# design.net
KiCad netlist of a schematic drawn in Altium Designer
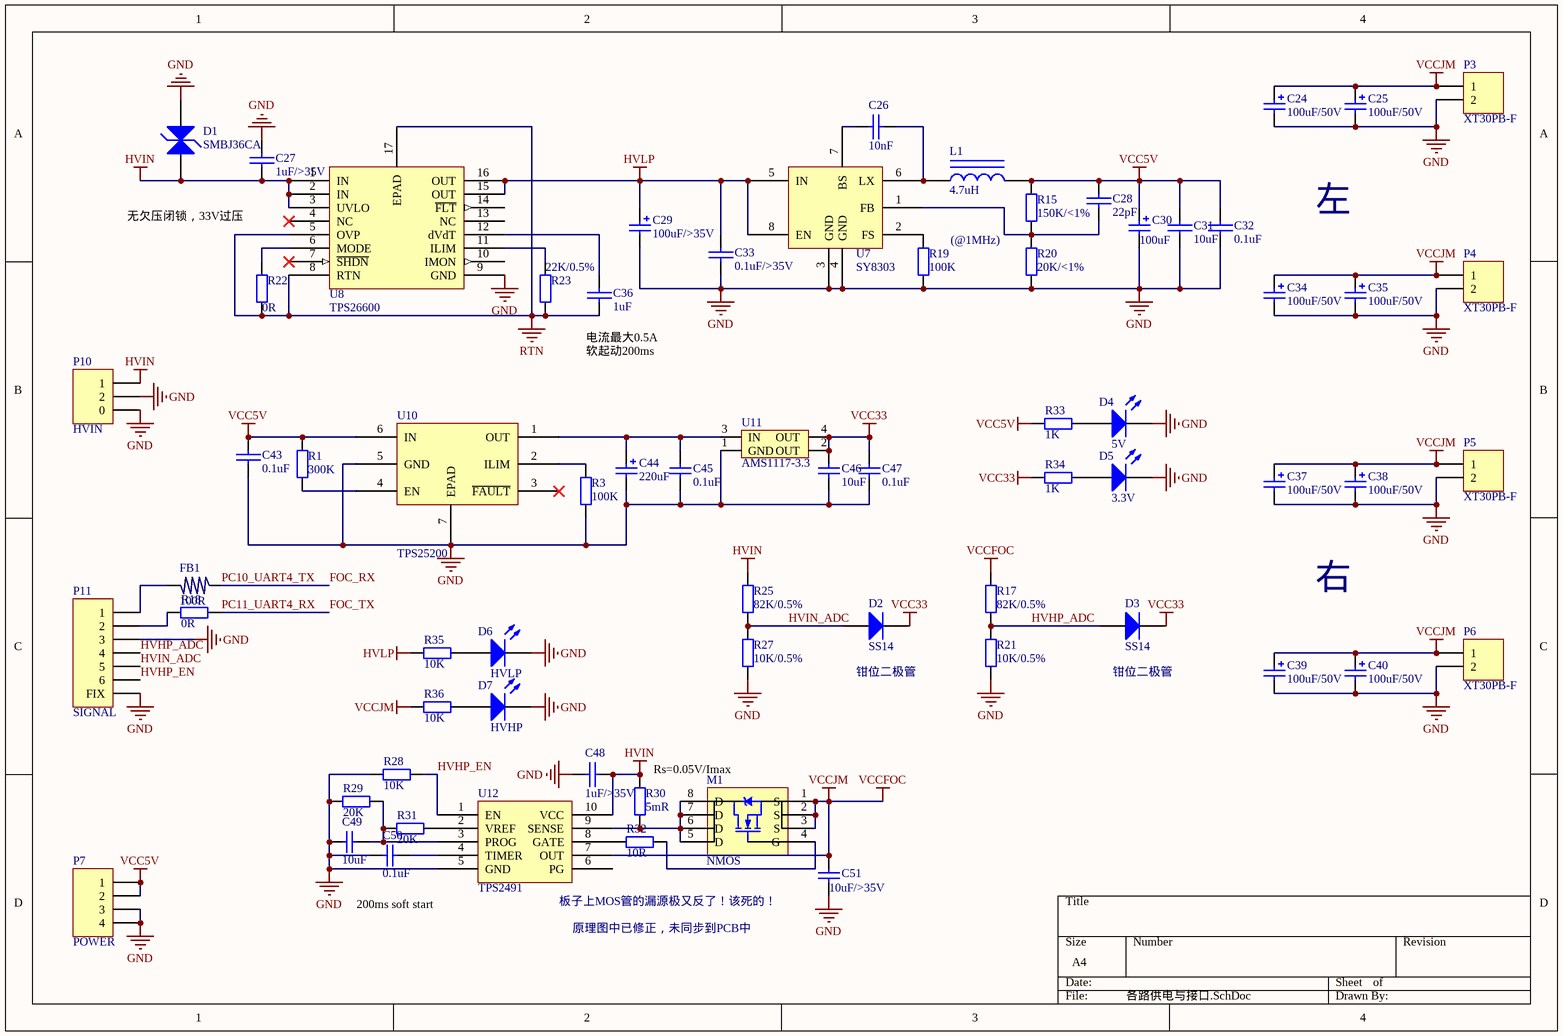
[diagram p0: 各路供电与接口.SchDoc]

(export (version "E")
  (design (tool "Eeschema 10.0.6"))
  (components
    (comp (ref "C24")
      (value "100uF/50V")
      (footprint "CS 6*6 - R")
      (description "Low ESR required")
      (fields (field (name "PUBLISHER") "Altium Limited"))
      (libsource (lib "Miscellaneous Devices") (part "Cap Pol2"))
    )
    (comp (ref "C25")
      (value "100uF/50V")
      (footprint "CS 6*6 - R")
      (description "Low ESR required")
      (fields (field (name "PUBLISHER") "Altium Limited"))
      (libsource (lib "Miscellaneous Devices") (part "Cap Pol2"))
    )
    (comp (ref "C26")
      (value "10nF")
      (footprint "C0805_M")
      (description "Capacitor")
      (libsource (lib "*") (part "CAP"))
    )
    (comp (ref "C27")
      (value "1uF/>35V")
      (footprint "C0805_M")
      (description "Capacitor")
      (libsource (lib "*") (part "CAP"))
    )
    (comp (ref "C28")
      (value "22pF")
      (footprint "C0805_M")
      (description "Capacitor")
      (libsource (lib "*") (part "CAP"))
    )
    (comp (ref "C29")
      (value "100uF/>35V")
      (footprint "CS 6*6 - R")
      (description "固态电容")
      (fields (field (name "PUBLISHER") "Altium Limited"))
      (libsource (lib "Miscellaneous Devices") (part "Cap Pol2"))
    )
    (comp (ref "C30")
      (value "100uF")
      (footprint "CS 6*6 - R")
      (description "固态电容")
      (fields (field (name "PUBLISHER") "Altium Limited"))
      (libsource (lib "Miscellaneous Devices") (part "Cap Pol2"))
    )
    (comp (ref "C31")
      (value "10uF")
      (footprint "C0805_M")
      (description "Capacitor")
      (libsource (lib "*") (part "CAP"))
    )
    (comp (ref "C32")
      (value "0.1uF")
      (footprint "C0805_M")
      (description "Capacitor")
      (libsource (lib "*") (part "CAP"))
    )
    (comp (ref "C33")
      (value "0.1uF/>35V")
      (footprint "C0805_M")
      (description "Capacitor")
      (libsource (lib "*") (part "CAP"))
    )
    (comp (ref "C34")
      (value "100uF/50V")
      (footprint "CS 6*6 - R")
      (description "Low ESR required")
      (fields (field (name "PUBLISHER") "Altium Limited"))
      (libsource (lib "Miscellaneous Devices") (part "Cap Pol2"))
    )
    (comp (ref "C35")
      (value "100uF/50V")
      (footprint "CS 6*6 - R")
      (description "Low ESR required")
      (fields (field (name "PUBLISHER") "Altium Limited"))
      (libsource (lib "Miscellaneous Devices") (part "Cap Pol2"))
    )
    (comp (ref "C36")
      (value "1uF")
      (footprint "C0805_M")
      (description "Capacitor")
      (libsource (lib "*") (part "CAP"))
    )
    (comp (ref "C37")
      (value "100uF/50V")
      (footprint "CS 6*6 - R")
      (description "Low ESR required")
      (fields (field (name "PUBLISHER") "Altium Limited"))
      (libsource (lib "Miscellaneous Devices") (part "Cap Pol2"))
    )
    (comp (ref "C38")
      (value "100uF/50V")
      (footprint "CS 6*6 - R")
      (description "Low ESR required")
      (fields (field (name "PUBLISHER") "Altium Limited"))
      (libsource (lib "Miscellaneous Devices") (part "Cap Pol2"))
    )
    (comp (ref "C39")
      (value "100uF/50V")
      (footprint "CS 6*6 - R")
      (description "Low ESR required")
      (fields (field (name "PUBLISHER") "Altium Limited"))
      (libsource (lib "Miscellaneous Devices") (part "Cap Pol2"))
    )
    (comp (ref "C40")
      (value "100uF/50V")
      (footprint "CS 6*6 - R")
      (description "Low ESR required")
      (fields (field (name "PUBLISHER") "Altium Limited"))
      (libsource (lib "Miscellaneous Devices") (part "Cap Pol2"))
    )
    (comp (ref "C43")
      (value "0.1uF")
      (footprint "C0805_M")
      (description "Capacitor")
      (libsource (lib "*") (part "CAP"))
    )
    (comp (ref "C44")
      (value "220uF")
      (footprint "CS 6*6 - R")
      (description "Polarized Capacitor (Axial)")
      (fields (field (name "PUBLISHER") "Altium Limited"))
      (libsource (lib "Miscellaneous Devices") (part "Cap Pol2"))
    )
    (comp (ref "C45")
      (value "0.1uF")
      (footprint "C0805_M")
      (description "Capacitor")
      (fields (field (name "PUBLISHER") "Altium Limited"))
      (libsource (lib "Miscellaneous Devices") (part "Cap"))
    )
    (comp (ref "C46")
      (value "10uF")
      (footprint "C0805_M")
      (description "Capacitor")
      (fields (field (name "PUBLISHER") "Altium Limited"))
      (libsource (lib "Miscellaneous Devices") (part "Cap"))
    )
    (comp (ref "C47")
      (value "0.1uF")
      (footprint "C0805_M")
      (description "Capacitor")
      (fields (field (name "PUBLISHER") "Altium Limited"))
      (libsource (lib "Miscellaneous Devices") (part "Cap"))
    )
    (comp (ref "C48")
      (value "1uF/>35V")
      (footprint "C0805_M")
      (description "Capacitor")
      (libsource (lib "*") (part "CAP"))
    )
    (comp (ref "C49")
      (value "10uF")
      (footprint "C0805_M")
      (description "Capacitor")
      (fields (field (name "PUBLISHER") "Altium Limited"))
      (libsource (lib "Miscellaneous Devices") (part "Cap"))
    )
    (comp (ref "C50")
      (value "0.1uF")
      (footprint "C0805_M")
      (description "Capacitor")
      (fields (field (name "PUBLISHER") "Altium Limited"))
      (libsource (lib "Miscellaneous Devices") (part "Cap"))
    )
    (comp (ref "C51")
      (value "10uF/>35V")
      (footprint "C0805_M")
      (description "Capacitor")
      (fields (field (name "PUBLISHER") "Altium Limited"))
      (libsource (lib "Miscellaneous Devices") (part "Cap"))
    )
    (comp (ref "D1")
      (value "SMBJ36CA")
      (footprint "1.07-二极管、整流桥:SMB")
      (libsource (lib "XL6005") (part "TVS"))
    )
    (comp (ref "D2")
      (value "SS14")
      (footprint "SOD-323")
      (description "Default Diode")
      (fields (field (name "PUBLISHER") "Altium Limited"))
      (libsource (lib "Miscellaneous Devices") (part "Diode"))
    )
    (comp (ref "D3")
      (value "SS14")
      (footprint "SOD-323")
      (description "Default Diode")
      (fields (field (name "PUBLISHER") "Altium Limited"))
      (libsource (lib "Miscellaneous Devices") (part "Diode"))
    )
    (comp (ref "D4")
      (value "5V")
      (footprint "LED0805_G")
      (description "Typical RED GaAs LED")
      (fields (field (name "PUBLISHER") "Altium Limited"))
      (libsource (lib "Miscellaneous Devices") (part "LED1"))
    )
    (comp (ref "D5")
      (value "3.3V")
      (footprint "LED0805_G")
      (description "Typical RED GaAs LED")
      (fields (field (name "PUBLISHER") "Altium Limited"))
      (libsource (lib "Miscellaneous Devices") (part "LED1"))
    )
    (comp (ref "D6")
      (value "HVLP")
      (footprint "LED0805_G")
      (description "Typical RED GaAs LED")
      (fields (field (name "PUBLISHER") "Altium Limited"))
      (libsource (lib "Miscellaneous Devices") (part "LED1"))
    )
    (comp (ref "D7")
      (value "HVHP")
      (footprint "LED0805_G")
      (description "Typical RED GaAs LED")
      (fields (field (name "PUBLISHER") "Altium Limited"))
      (libsource (lib "Miscellaneous Devices") (part "LED1"))
    )
    (comp (ref "FB1") (value "100R") (footprint "R0805_M") (libsource (lib "EXPLORER") (part "L")))
    (comp (ref "L1")
      (value "4.7uH")
      (footprint "L-SMD-0630")
      (description "Magnetic-Core Inductor")
      (fields (field (name "PUBLISHER") "Altium Limited"))
      (libsource (lib "Miscellaneous Devices") (part "Inductor Iron"))
    )
    (comp (ref "M1") (value "NMOS") (footprint "DFN8L-5X6") (libsource (lib "XL6005") (part "NMOS_IC")))
    (comp (ref "P3")
      (value "XT30PB-F")
      (footprint "XT30PB-F")
      (description "Header, 2-Pin")
      (fields (field (name "PUBLISHER") "Altium Limited"))
      (libsource (lib "Miscellaneous Connectors") (part "Header 2"))
    )
    (comp (ref "P4")
      (value "XT30PB-F")
      (footprint "XT30PB-F")
      (description "Header, 2-Pin")
      (fields (field (name "PUBLISHER") "Altium Limited"))
      (libsource (lib "Miscellaneous Connectors") (part "Header 2"))
    )
    (comp (ref "P5")
      (value "XT30PB-F")
      (footprint "XT30PB-F")
      (description "Header, 2-Pin")
      (fields (field (name "PUBLISHER") "Altium Limited"))
      (libsource (lib "Miscellaneous Connectors") (part "Header 2"))
    )
    (comp (ref "P6")
      (value "XT30PB-F")
      (footprint "XT30PB-F")
      (description "Header, 2-Pin")
      (fields (field (name "PUBLISHER") "Altium Limited"))
      (libsource (lib "Miscellaneous Connectors") (part "Header 2"))
    )
    (comp (ref "P7")
      (value "POWER")
      (footprint "XH2.54-LI-4P")
      (description "Header, 4-Pin")
      (fields (field (name "PUBLISHER") "Altium Limited"))
      (libsource (lib "Miscellaneous Connectors") (part "Header 4"))
    )
    (comp (ref "P10")
      (value "HVIN")
      (footprint "XT60PW-M")
      (description "Header, 3-Pin")
      (fields (field (name "PUBLISHER") "Altium Limited"))
      (libsource (lib "Miscellaneous Connectors") (part "Header 3"))
    )
    (comp (ref "P11")
      (value "SIGNAL")
      (footprint "SH1.0-LT-6P")
      (description "Header, 7-Pin")
      (fields (field (name "PUBLISHER") "Altium Limited"))
      (libsource (lib "Miscellaneous Connectors") (part "Header 7"))
    )
    (comp (ref "R1")
      (value "300K")
      (footprint "R0805_M")
      (description "Resistor")
      (fields (field (name "PUBLISHER") "Altium Limited"))
      (libsource (lib "Miscellaneous Devices") (part "Res2"))
    )
    (comp (ref "R3")
      (value "100K")
      (footprint "R0805_M")
      (description "Resistor")
      (fields (field (name "PUBLISHER") "Altium Limited"))
      (libsource (lib "Miscellaneous Devices") (part "Res2"))
    )
    (comp (ref "R15")
      (value "150K/<1%")
      (footprint "R0805_M")
      (description "Resistor")
      (fields (field (name "PUBLISHER") "Altium Limited"))
      (libsource (lib "") (part "Res2_1"))
    )
    (comp (ref "R17")
      (value "82K/0.5%")
      (footprint "R0805_M")
      (description "Resistor")
      (fields (field (name "PUBLISHER") "Altium Limited"))
      (libsource (lib "") (part "Res2_1"))
    )
    (comp (ref "R18")
      (value "0R")
      (footprint "R0805_M")
      (description "Resistor")
      (fields (field (name "PUBLISHER") "Altium Limited"))
      (libsource (lib "") (part "Res2_2"))
    )
    (comp (ref "R19")
      (value "100K")
      (footprint "R0805_M")
      (description "Resistor")
      (fields (field (name "PUBLISHER") "Altium Limited"))
      (libsource (lib "") (part "Res2_1"))
    )
    (comp (ref "R20")
      (value "20K/<1%")
      (footprint "R0805_M")
      (description "Resistor")
      (fields (field (name "PUBLISHER") "Altium Limited"))
      (libsource (lib "") (part "Res2_1"))
    )
    (comp (ref "R21")
      (value "10K/0.5%")
      (footprint "R0805_M")
      (description "Resistor")
      (fields (field (name "PUBLISHER") "Altium Limited"))
      (libsource (lib "") (part "Res2_1"))
    )
    (comp (ref "R22")
      (value "0R")
      (footprint "R0805_M")
      (description "Resistor")
      (fields (field (name "PUBLISHER") "Altium Limited"))
      (libsource (lib "") (part "Res2_1"))
    )
    (comp (ref "R23")
      (value "22K/0.5%")
      (footprint "R0805_M")
      (description "Resistor")
      (fields (field (name "PUBLISHER") "Altium Limited"))
      (libsource (lib "") (part "Res2_1"))
    )
    (comp (ref "R25")
      (value "82K/0.5%")
      (footprint "R0805_M")
      (description "Resistor")
      (fields (field (name "PUBLISHER") "Altium Limited"))
      (libsource (lib "") (part "Res2_1"))
    )
    (comp (ref "R27")
      (value "10K/0.5%")
      (footprint "R0805_M")
      (description "Resistor")
      (fields (field (name "PUBLISHER") "Altium Limited"))
      (libsource (lib "") (part "Res2_1"))
    )
    (comp (ref "R28")
      (value "10K")
      (footprint "R0805_M")
      (description "Resistor")
      (fields (field (name "PUBLISHER") "Altium Limited"))
      (libsource (lib "") (part "Res2_2"))
    )
    (comp (ref "R29")
      (value "20K")
      (footprint "R0805_M")
      (description "Resistor")
      (fields (field (name "PUBLISHER") "Altium Limited"))
      (libsource (lib "") (part "Res2_2"))
    )
    (comp (ref "R30")
      (value "5mR")
      (footprint "R2512_M")
      (description "Resistor")
      (fields (field (name "PUBLISHER") "Altium Limited"))
      (libsource (lib "Miscellaneous Devices") (part "Res2"))
    )
    (comp (ref "R31")
      (value "20K")
      (footprint "R0805_M")
      (description "Resistor")
      (fields (field (name "PUBLISHER") "Altium Limited"))
      (libsource (lib "") (part "Res2_2"))
    )
    (comp (ref "R32")
      (value "10R")
      (footprint "R0805_M")
      (description "Resistor")
      (fields (field (name "PUBLISHER") "Altium Limited"))
      (libsource (lib "") (part "Res2_2"))
    )
    (comp (ref "R33")
      (value "1K")
      (footprint "R0805_M")
      (description "Resistor")
      (fields (field (name "PUBLISHER") "Altium Limited"))
      (libsource (lib "") (part "Res2_2"))
    )
    (comp (ref "R34")
      (value "1K")
      (footprint "R0805_M")
      (description "Resistor")
      (fields (field (name "PUBLISHER") "Altium Limited"))
      (libsource (lib "") (part "Res2_2"))
    )
    (comp (ref "R35")
      (value "10K")
      (footprint "R0805_M")
      (description "Resistor")
      (fields (field (name "PUBLISHER") "Altium Limited"))
      (libsource (lib "") (part "Res2_2"))
    )
    (comp (ref "R36")
      (value "10K")
      (footprint "R0805_M")
      (description "Resistor")
      (fields (field (name "PUBLISHER") "Altium Limited"))
      (libsource (lib "") (part "Res2_2"))
    )
    (comp (ref "U7") (value "SY8303") (footprint "SOT23-8L") (libsource (lib "7688A原理图封装") (part "SY8303")))
    (comp (ref "U8") (value "TPS26600") (footprint "ETSSOP16_M") (libsource (lib "XL6005") (part "TPS26600")))
    (comp (ref "U10")
      (value "TPS25200")
      (footprint "WSON-6")
      (libsource (lib "7688A原理图封装") (part "TPS25200"))
    )
    (comp (ref "U11")
      (value "AMS1117-3.3")
      (footprint "2.02-SOT封装:SOT223_M")
      (libsource (lib "Explorer STM32F407封装库") (part "AMS1117"))
    )
    (comp (ref "U12") (value "TPS2491") (footprint "VSSOP10") (libsource (lib "XL6005") (part "TPS2491")))
  )
  (nets
    (net (code "1") (name "/FOC_RX") (class "Default") (node (ref "FB1") (pin "1") (pintype "passive")))
    (net (code "2") (name "/FOC_TX") (class "Default")
      (node (ref "R18") (pin "1") (pinfunction "1_1") (pintype "passive"))
    )
    (net (code "3") (name "/HVHP_ADC") (class "Default")
      (node (ref "D3") (pin "1") (pinfunction "A_1") (pintype "passive"))
      (node (ref "P11") (pin "4") (pinfunction "4_4") (pintype "passive"))
      (node (ref "R17") (pin "2") (pinfunction "2_2") (pintype "passive"))
      (node (ref "R21") (pin "1") (pinfunction "1_1") (pintype "passive"))
    )
    (net (code "4") (name "/HVHP_EN") (class "Default")
      (node (ref "P11") (pin "6") (pinfunction "6_6") (pintype "passive"))
      (node (ref "R28") (pin "1") (pinfunction "1_1") (pintype "passive"))
      (node (ref "U12") (pin "1") (pinfunction "EN_1") (pintype "passive"))
    )
    (net (code "5") (name "/HVIN_ADC") (class "Default")
      (node (ref "D2") (pin "1") (pinfunction "A_1") (pintype "passive"))
      (node (ref "P11") (pin "5") (pinfunction "5_5") (pintype "passive"))
      (node (ref "R25") (pin "2") (pinfunction "2_2") (pintype "passive"))
      (node (ref "R27") (pin "1") (pinfunction "1_1") (pintype "passive"))
    )
    (net (code "6") (name "GND") (class "Default")
      (node (ref "C24") (pin "2") (pinfunction "2_2") (pintype "passive"))
      (node (ref "C25") (pin "2") (pinfunction "2_2") (pintype "passive"))
      (node (ref "C27") (pin "2") (pinfunction "2_2") (pintype "passive"))
      (node (ref "C29") (pin "2") (pinfunction "2_2") (pintype "passive"))
      (node (ref "C30") (pin "2") (pinfunction "2_2") (pintype "passive"))
      (node (ref "C31") (pin "1") (pinfunction "1_1") (pintype "passive"))
      (node (ref "C32") (pin "1") (pinfunction "1_1") (pintype "passive"))
      (node (ref "C33") (pin "1") (pinfunction "1_1") (pintype "passive"))
      (node (ref "C34") (pin "2") (pinfunction "2_2") (pintype "passive"))
      (node (ref "C35") (pin "2") (pinfunction "2_2") (pintype "passive"))
      (node (ref "C37") (pin "2") (pinfunction "2_2") (pintype "passive"))
      (node (ref "C38") (pin "2") (pinfunction "2_2") (pintype "passive"))
      (node (ref "C39") (pin "2") (pinfunction "2_2") (pintype "passive"))
      (node (ref "C40") (pin "2") (pinfunction "2_2") (pintype "passive"))
      (node (ref "C43") (pin "2") (pinfunction "2_2") (pintype "passive"))
      (node (ref "C44") (pin "2") (pinfunction "2_2") (pintype "passive"))
      (node (ref "C45") (pin "1") (pinfunction "1_1") (pintype "passive"))
      (node (ref "C46") (pin "1") (pinfunction "1_1") (pintype "passive"))
      (node (ref "C47") (pin "1") (pinfunction "1_1") (pintype "passive"))
      (node (ref "C48") (pin "1") (pinfunction "1_1") (pintype "passive"))
      (node (ref "C49") (pin "1") (pinfunction "1_1") (pintype "passive"))
      (node (ref "C50") (pin "1") (pinfunction "1_1") (pintype "passive"))
      (node (ref "C51") (pin "1") (pinfunction "1_1") (pintype "passive"))
      (node (ref "D1") (pin "1") (pinfunction "A_1") (pintype "passive"))
      (node (ref "D4") (pin "2") (pinfunction "K_2") (pintype "passive"))
      (node (ref "D5") (pin "2") (pinfunction "K_2") (pintype "passive"))
      (node (ref "D6") (pin "2") (pinfunction "K_2") (pintype "passive"))
      (node (ref "D7") (pin "2") (pinfunction "K_2") (pintype "passive"))
      (node (ref "P10") (pin "0") (pinfunction "0_0") (pintype "passive"))
      (node (ref "P10") (pin "2") (pinfunction "2_2") (pintype "passive"))
      (node (ref "P11") (pin "0") (pinfunction "FIX_0") (pintype "passive"))
      (node (ref "P11") (pin "3") (pinfunction "3_3") (pintype "passive"))
      (node (ref "P3") (pin "2") (pinfunction "2_2") (pintype "passive"))
      (node (ref "P4") (pin "2") (pinfunction "2_2") (pintype "passive"))
      (node (ref "P5") (pin "2") (pinfunction "2_2") (pintype "passive"))
      (node (ref "P6") (pin "2") (pinfunction "2_2") (pintype "passive"))
      (node (ref "P7") (pin "3") (pinfunction "3_3") (pintype "passive"))
      (node (ref "P7") (pin "4") (pinfunction "4_4") (pintype "passive"))
      (node (ref "R19") (pin "2") (pinfunction "2_2") (pintype "passive"))
      (node (ref "R20") (pin "2") (pinfunction "2_2") (pintype "passive"))
      (node (ref "R21") (pin "2") (pinfunction "2_2") (pintype "passive"))
      (node (ref "R27") (pin "2") (pinfunction "2_2") (pintype "passive"))
      (node (ref "R28") (pin "2") (pinfunction "2_2") (pintype "passive"))
      (node (ref "R29") (pin "2") (pinfunction "2_2") (pintype "passive"))
      (node (ref "R3") (pin "1") (pinfunction "1_1") (pintype "passive"))
      (node (ref "U10") (pin "5") (pinfunction "GND_5") (pintype "passive"))
      (node (ref "U10") (pin "7") (pinfunction "EPAD_7") (pintype "passive"))
      (node (ref "U11") (pin "1") (pinfunction "GND_1") (pintype "passive"))
      (node (ref "U12") (pin "5") (pinfunction "GND_5") (pintype "passive"))
      (node (ref "U7") (pin "3") (pinfunction "GND_3") (pintype "passive"))
      (node (ref "U7") (pin "4") (pinfunction "GND_4") (pintype "passive"))
      (node (ref "U8") (pin "9") (pinfunction "GND_9") (pintype "passive"))
    )
    (net (code "7") (name "HVIN") (class "Default")
      (node (ref "C27") (pin "1") (pinfunction "1_1") (pintype "passive"))
      (node (ref "C48") (pin "2") (pinfunction "2_2") (pintype "passive"))
      (node (ref "D1") (pin "2") (pinfunction "K_2") (pintype "passive"))
      (node (ref "P10") (pin "1") (pinfunction "1_1") (pintype "passive"))
      (node (ref "R25") (pin "1") (pinfunction "1_1") (pintype "passive"))
      (node (ref "R30") (pin "2") (pinfunction "2_2") (pintype "passive"))
      (node (ref "U12") (pin "10") (pinfunction "VCC_10") (pintype "passive"))
      (node (ref "U8") (pin "1") (pinfunction "IN_1") (pintype "passive"))
      (node (ref "U8") (pin "2") (pinfunction "IN_2") (pintype "passive"))
      (node (ref "U8") (pin "3") (pinfunction "UVLO_3") (pintype "passive"))
    )
    (net (code "8") (name "HVLP") (class "Default")
      (node (ref "C29") (pin "1") (pinfunction "1_1") (pintype "passive"))
      (node (ref "C33") (pin "2") (pinfunction "2_2") (pintype "passive"))
      (node (ref "R35") (pin "2") (pinfunction "2_2") (pintype "passive"))
      (node (ref "U7") (pin "5") (pinfunction "IN_5") (pintype "passive"))
      (node (ref "U7") (pin "8") (pinfunction "EN_8") (pintype "passive"))
      (node (ref "U8") (pin "15") (pinfunction "OUT_15") (pintype "passive"))
      (node (ref "U8") (pin "16") (pinfunction "OUT_16") (pintype "passive"))
    )
    (net (code "9") (name "Net-(D4-A)") (class "Default")
      (node (ref "D4") (pin "1") (pinfunction "A_1") (pintype "passive"))
      (node (ref "R33") (pin "1") (pinfunction "1_1") (pintype "passive"))
    )
    (net (code "10") (name "Net-(D5-A)") (class "Default")
      (node (ref "D5") (pin "1") (pinfunction "A_1") (pintype "passive"))
      (node (ref "R34") (pin "1") (pinfunction "1_1") (pintype "passive"))
    )
    (net (code "11") (name "Net-(D6-A)") (class "Default")
      (node (ref "D6") (pin "1") (pinfunction "A_1") (pintype "passive"))
      (node (ref "R35") (pin "1") (pinfunction "1_1") (pintype "passive"))
    )
    (net (code "12") (name "Net-(D7-A)") (class "Default")
      (node (ref "D7") (pin "1") (pinfunction "A_1") (pintype "passive"))
      (node (ref "R36") (pin "1") (pinfunction "1_1") (pintype "passive"))
    )
    (net (code "13") (name "Net-(FB1-Pad2)") (class "Default")
      (node (ref "FB1") (pin "2") (pintype "passive"))
      (node (ref "P11") (pin "1") (pinfunction "1_1") (pintype "passive"))
    )
    (net (code "14") (name "Net-(M1-G)") (class "Default")
      (node (ref "M1") (pin "4") (pinfunction "G_4") (pintype "passive"))
      (node (ref "R32") (pin "1") (pinfunction "1_1") (pintype "passive"))
    )
    (net (code "15") (name "Net-(P11-Pad2)") (class "Default")
      (node (ref "P11") (pin "2") (pinfunction "2_2") (pintype "passive"))
      (node (ref "R18") (pin "2") (pinfunction "2_2") (pintype "passive"))
    )
    (net (code "16") (name "Net-(U7-BS)") (class "Default")
      (node (ref "C26") (pin "1") (pinfunction "1_1") (pintype "passive"))
      (node (ref "U7") (pin "7") (pinfunction "BS_7") (pintype "passive"))
    )
    (net (code "17") (name "Net-(U7-FB)") (class "Default")
      (node (ref "C28") (pin "1") (pinfunction "1_1") (pintype "passive"))
      (node (ref "R15") (pin "2") (pinfunction "2_2") (pintype "passive"))
      (node (ref "R20") (pin "1") (pinfunction "1_1") (pintype "passive"))
      (node (ref "U7") (pin "1") (pinfunction "FB_1") (pintype "passive"))
    )
    (net (code "18") (name "Net-(U7-FS)") (class "Default")
      (node (ref "R19") (pin "1") (pinfunction "1_1") (pintype "passive"))
      (node (ref "U7") (pin "2") (pinfunction "FS_2") (pintype "passive"))
    )
    (net (code "19") (name "Net-(U7-LX)") (class "Default")
      (node (ref "C26") (pin "2") (pinfunction "2_2") (pintype "passive"))
      (node (ref "L1") (pin "1") (pinfunction "1_1") (pintype "passive"))
      (node (ref "U7") (pin "6") (pinfunction "LX_6") (pintype "passive"))
    )
    (net (code "20") (name "Net-(U8-ILIM)") (class "Default")
      (node (ref "R23") (pin "1") (pinfunction "1_1") (pintype "passive"))
      (node (ref "U8") (pin "11") (pinfunction "ILIM_11") (pintype "passive"))
    )
    (net (code "21") (name "Net-(U8-MODE)") (class "Default")
      (node (ref "R22") (pin "1") (pinfunction "1_1") (pintype "passive"))
      (node (ref "U8") (pin "6") (pinfunction "MODE_6") (pintype "passive"))
    )
    (net (code "22") (name "Net-(U8-dVdT)") (class "Default")
      (node (ref "C36") (pin "1") (pinfunction "1_1") (pintype "passive"))
      (node (ref "U8") (pin "12") (pinfunction "dVdT_12") (pintype "passive"))
    )
    (net (code "23") (name "Net-(U10-EN)") (class "Default")
      (node (ref "R1") (pin "1") (pinfunction "1_1") (pintype "passive"))
      (node (ref "U10") (pin "4") (pinfunction "EN_4") (pintype "passive"))
    )
    (net (code "24") (name "Net-(U10-ILIM)") (class "Default")
      (node (ref "R3") (pin "2") (pinfunction "2_2") (pintype "passive"))
      (node (ref "U10") (pin "2") (pinfunction "ILIM_2") (pintype "passive"))
    )
    (net (code "25") (name "Net-(U10-OUT)") (class "Default")
      (node (ref "C44") (pin "1") (pinfunction "1_1") (pintype "passive"))
      (node (ref "C45") (pin "2") (pinfunction "2_2") (pintype "passive"))
      (node (ref "U10") (pin "1") (pinfunction "OUT_1") (pintype "passive"))
      (node (ref "U11") (pin "3") (pinfunction "IN_3") (pintype "passive"))
    )
    (net (code "26") (name "Net-(U12-GATE)") (class "Default")
      (node (ref "R32") (pin "2") (pinfunction "2_2") (pintype "passive"))
      (node (ref "U12") (pin "8") (pinfunction "GATE_8") (pintype "passive"))
    )
    (net (code "27") (name "Net-(U12-PROG)") (class "Default")
      (node (ref "C49") (pin "2") (pinfunction "2_2") (pintype "passive"))
      (node (ref "R29") (pin "1") (pinfunction "1_1") (pintype "passive"))
      (node (ref "R31") (pin "2") (pinfunction "2_2") (pintype "passive"))
      (node (ref "U12") (pin "3") (pinfunction "PROG_3") (pintype "passive"))
    )
    (net (code "28") (name "Net-(U12-SENSE)") (class "Default")
      (node (ref "M1") (pin "5") (pinfunction "D_5") (pintype "passive"))
      (node (ref "M1") (pin "6") (pinfunction "D_6") (pintype "passive"))
      (node (ref "M1") (pin "7") (pinfunction "D_7") (pintype "passive"))
      (node (ref "M1") (pin "8") (pinfunction "D_8") (pintype "passive"))
      (node (ref "R30") (pin "1") (pinfunction "1_1") (pintype "passive"))
      (node (ref "U12") (pin "9") (pinfunction "SENSE_9") (pintype "passive"))
    )
    (net (code "29") (name "Net-(U12-TIMER)") (class "Default")
      (node (ref "C50") (pin "2") (pinfunction "2_2") (pintype "passive"))
      (node (ref "U12") (pin "4") (pinfunction "TIMER_4") (pintype "passive"))
    )
    (net (code "30") (name "Net-(U12-VREF)") (class "Default")
      (node (ref "R31") (pin "1") (pinfunction "1_1") (pintype "passive"))
      (node (ref "U12") (pin "2") (pinfunction "VREF_2") (pintype "passive"))
    )
    (net (code "31") (name "RTN") (class "Default")
      (node (ref "C36") (pin "2") (pinfunction "2_2") (pintype "passive"))
      (node (ref "R22") (pin "2") (pinfunction "2_2") (pintype "passive"))
      (node (ref "R23") (pin "2") (pinfunction "2_2") (pintype "passive"))
      (node (ref "U8") (pin "17") (pinfunction "EPAD_17") (pintype "passive"))
      (node (ref "U8") (pin "5") (pinfunction "OVP_5") (pintype "passive"))
      (node (ref "U8") (pin "8") (pinfunction "RTN_8") (pintype "passive"))
    )
    (net (code "32") (name "VCC5V") (class "Default")
      (node (ref "C28") (pin "2") (pinfunction "2_2") (pintype "passive"))
      (node (ref "C30") (pin "1") (pinfunction "1_1") (pintype "passive"))
      (node (ref "C31") (pin "2") (pinfunction "2_2") (pintype "passive"))
      (node (ref "C32") (pin "2") (pinfunction "2_2") (pintype "passive"))
      (node (ref "C43") (pin "1") (pinfunction "1_1") (pintype "passive"))
      (node (ref "L1") (pin "2") (pinfunction "2_2") (pintype "passive"))
      (node (ref "P7") (pin "1") (pinfunction "1_1") (pintype "passive"))
      (node (ref "P7") (pin "2") (pinfunction "2_2") (pintype "passive"))
      (node (ref "R1") (pin "2") (pinfunction "2_2") (pintype "passive"))
      (node (ref "R15") (pin "1") (pinfunction "1_1") (pintype "passive"))
      (node (ref "R33") (pin "2") (pinfunction "2_2") (pintype "passive"))
      (node (ref "U10") (pin "6") (pinfunction "IN_6") (pintype "passive"))
    )
    (net (code "33") (name "VCC33") (class "Default")
      (node (ref "C46") (pin "2") (pinfunction "2_2") (pintype "passive"))
      (node (ref "C47") (pin "2") (pinfunction "2_2") (pintype "passive"))
      (node (ref "D2") (pin "2") (pinfunction "K_2") (pintype "passive"))
      (node (ref "D3") (pin "2") (pinfunction "K_2") (pintype "passive"))
      (node (ref "R34") (pin "2") (pinfunction "2_2") (pintype "passive"))
      (node (ref "U11") (pin "2") (pinfunction "OUT_2") (pintype "passive"))
      (node (ref "U11") (pin "4") (pinfunction "OUT_4") (pintype "passive"))
    )
    (net (code "34") (name "VCCFOC") (class "Default")
      (node (ref "C24") (pin "1") (pinfunction "1_1") (pintype "passive"))
      (node (ref "C25") (pin "1") (pinfunction "1_1") (pintype "passive"))
      (node (ref "C34") (pin "1") (pinfunction "1_1") (pintype "passive"))
      (node (ref "C35") (pin "1") (pinfunction "1_1") (pintype "passive"))
      (node (ref "C37") (pin "1") (pinfunction "1_1") (pintype "passive"))
      (node (ref "C38") (pin "1") (pinfunction "1_1") (pintype "passive"))
      (node (ref "C39") (pin "1") (pinfunction "1_1") (pintype "passive"))
      (node (ref "C40") (pin "1") (pinfunction "1_1") (pintype "passive"))
      (node (ref "C51") (pin "2") (pinfunction "2_2") (pintype "passive"))
      (node (ref "M1") (pin "1") (pinfunction "S_1") (pintype "passive"))
      (node (ref "M1") (pin "2") (pinfunction "S_2") (pintype "passive"))
      (node (ref "M1") (pin "3") (pinfunction "S_3") (pintype "passive"))
      (node (ref "P3") (pin "1") (pinfunction "1_1") (pintype "passive"))
      (node (ref "P4") (pin "1") (pinfunction "1_1") (pintype "passive"))
      (node (ref "P5") (pin "1") (pinfunction "1_1") (pintype "passive"))
      (node (ref "P6") (pin "1") (pinfunction "1_1") (pintype "passive"))
      (node (ref "R17") (pin "1") (pinfunction "1_1") (pintype "passive"))
      (node (ref "R36") (pin "2") (pinfunction "2_2") (pintype "passive"))
      (node (ref "U12") (pin "7") (pinfunction "OUT_7") (pintype "passive"))
    )
    (net (code "35") (name "unconnected-(U8-IMON-Pad10)") (class "Default")
      (node (ref "U8") (pin "10") (pinfunction "IMON_10") (pintype "output"))
    )
    (net (code "36") (name "unconnected-(U8-NC-Pad4)") (class "Default")
      (node (ref "U8") (pin "4") (pinfunction "NC_4") (pintype "passive+no_connect"))
    )
    (net (code "37") (name "unconnected-(U8-NC-Pad13)") (class "Default")
      (node (ref "U8") (pin "13") (pinfunction "NC_13") (pintype "passive"))
    )
    (net (code "38") (name "unconnected-(U8-~{FLT}-Pad14)") (class "Default")
      (node (ref "U8") (pin "14") (pinfunction "~{FLT}_14") (pintype "output"))
    )
    (net (code "39") (name "unconnected-(U8-~{SHDN}-Pad7)") (class "Default")
      (node (ref "U8") (pin "7") (pinfunction "~{SHDN}_7") (pintype "input+no_connect"))
    )
    (net (code "40") (name "unconnected-(U10-~{FAULT}-Pad3)") (class "Default")
      (node (ref "U10") (pin "3") (pinfunction "~{FAULT}_3") (pintype "passive+no_connect"))
    )
    (net (code "41") (name "unconnected-(U12-PG-Pad6)") (class "Default")
      (node (ref "U12") (pin "6") (pinfunction "PG_6") (pintype "passive"))
    )
  )
)
